# actuatorDriver.net
KiCad netlist of a schematic drawn in Altium Designer
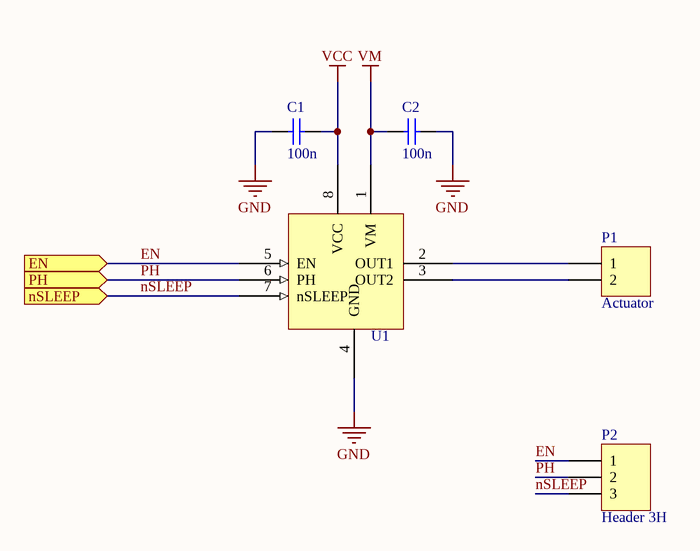
[diagram p0: actuatorDriver.SchDoc]

(export (version "E")
  (design (tool "Eeschema 10.0.6"))
  (components
    (comp (ref "C1")
      (value "100n")
      (footprint "Footprint:CAP 0603/1608")
      (libsource (lib "Miscellaneous Devices") (part "Cap"))
    )
    (comp (ref "C2")
      (value "100n")
      (footprint "CAP 0603/1608")
      (libsource (lib "Miscellaneous Devices") (part "Cap"))
    )
    (comp (ref "P1")
      (value "Actuator")
      (footprint "HDR1X2")
      (description "Header, 2-Pin")
      (fields (field (name "PUBLISHER") "Altium Limited"))
      (libsource (lib "Miscellaneous Connectors") (part "Header 2"))
    )
    (comp (ref "P2")
      (value "Header 3H")
      (footprint "HDR1X3")
      (libsource (lib "Miscellaneous Connectors") (part "Header 3H"))
    )
    (comp (ref "U1")
      (value "DRV8838")
      (footprint "S-PWSON-N8")
      (description "Moteur Driver [H - bridge]")
      (libsource (lib "ComponentLib") (part "DRV8838"))
    )
  )
  (nets
    (net (code "1") (name "/EN") (class "Default")
      (node (ref "P2") (pin "1") (pinfunction "1_1") (pintype "passive"))
      (node (ref "U1") (pin "5") (pinfunction "EN_5") (pintype "input"))
    )
    (net (code "2") (name "/PH") (class "Default")
      (node (ref "P2") (pin "2") (pinfunction "2_2") (pintype "passive"))
      (node (ref "U1") (pin "6") (pinfunction "PH_6") (pintype "input"))
    )
    (net (code "3") (name "/nSLEEP") (class "Default")
      (node (ref "P2") (pin "3") (pinfunction "3_3") (pintype "passive"))
      (node (ref "U1") (pin "7") (pinfunction "nSLEEP_7") (pintype "input"))
    )
    (net (code "4") (name "GND") (class "Default")
      (node (ref "C1") (pin "2") (pinfunction "2_2") (pintype "passive"))
      (node (ref "C2") (pin "1") (pinfunction "1_1") (pintype "passive"))
      (node (ref "U1") (pin "4") (pinfunction "GND_4") (pintype "power_in"))
    )
    (net (code "5") (name "Net-(U1-OUT1)") (class "Default")
      (node (ref "P1") (pin "1") (pinfunction "1_1") (pintype "passive"))
      (node (ref "U1") (pin "2") (pinfunction "OUT1_2") (pintype "passive"))
    )
    (net (code "6") (name "Net-(U1-OUT2)") (class "Default")
      (node (ref "P1") (pin "2") (pinfunction "2_2") (pintype "passive"))
      (node (ref "U1") (pin "3") (pinfunction "OUT2_3") (pintype "passive"))
    )
    (net (code "7") (name "VCC") (class "Default")
      (node (ref "C1") (pin "1") (pinfunction "1_1") (pintype "passive"))
      (node (ref "U1") (pin "8") (pinfunction "VCC_8") (pintype "power_in"))
    )
    (net (code "8") (name "VM") (class "Default")
      (node (ref "C2") (pin "2") (pinfunction "2_2") (pintype "passive"))
      (node (ref "U1") (pin "1") (pinfunction "VM_1") (pintype "power_in"))
    )
  )
)
